# Sheet1.net
KiCad netlist of a schematic drawn in Altium Designer
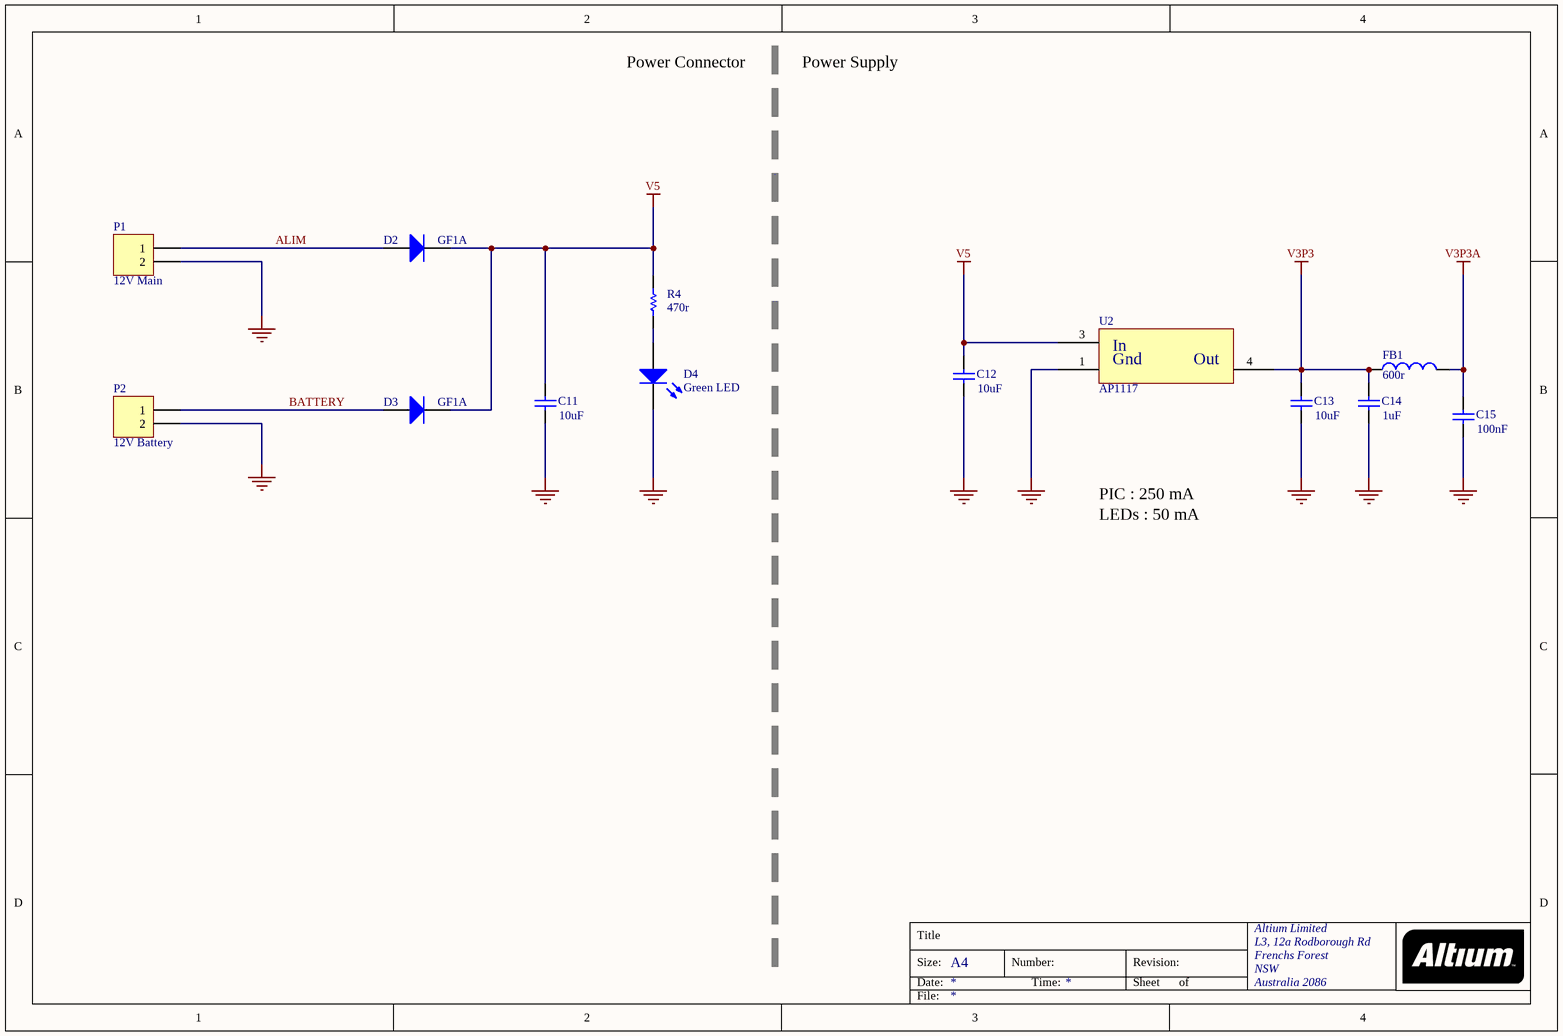
[diagram p0: Sheet1.SchDoc]

(export (version "E")
  (design (tool "Eeschema 10.0.6"))
  (components
    (comp (ref "C11")
      (value "10uF")
      (footprint "RAD-0.3")
      (description "Capacitor")
      (fields (field (name "PUBLISHER") "Altium Limited"))
      (libsource (lib "Miscellaneous Devices") (part "Cap"))
    )
    (comp (ref "C12")
      (value "10uF")
      (footprint "RAD-0.3")
      (description "Capacitor")
      (fields (field (name "Comment") "Cap") (field (name "PUBLISHER") "Altium Limited"))
      (libsource (lib "Miscellaneous Devices") (part "Cap"))
    )
    (comp (ref "C13")
      (value "10uF")
      (footprint "RAD-0.3")
      (description "Capacitor")
      (fields (field (name "Comment") "Cap") (field (name "PUBLISHER") "Altium Limited"))
      (libsource (lib "Miscellaneous Devices") (part "Cap"))
    )
    (comp (ref "C14")
      (value "1uF")
      (footprint "RAD-0.3")
      (description "Capacitor")
      (fields (field (name "Comment") "Cap") (field (name "PUBLISHER") "Altium Limited"))
      (libsource (lib "Miscellaneous Devices") (part "Cap"))
    )
    (comp (ref "C15")
      (value "100nF")
      (footprint "RAD-0.3")
      (description "Capacitor")
      (fields (field (name "Comment") "Cap") (field (name "PUBLISHER") "Altium Limited"))
      (libsource (lib "Miscellaneous Devices") (part "Cap"))
    )
    (comp (ref "D2")
      (value "GF1A")
      (footprint "SMC")
      (description "Default Diode")
      (fields (field (name "PUBLISHER") "Altium Limited"))
      (libsource (lib "Miscellaneous Devices") (part "Diode"))
    )
    (comp (ref "D3")
      (value "GF1A")
      (footprint "SMC")
      (description "Default Diode")
      (fields (field (name "PUBLISHER") "Altium Limited"))
      (libsource (lib "Miscellaneous Devices") (part "Diode"))
    )
    (comp (ref "D4")
      (value "Green LED")
      (footprint "LED-0")
      (description "Typical INFRARED GaAs LED")
      (fields (field (name "PUBLISHER") "Altium Limited"))
      (libsource (lib "Miscellaneous Devices") (part "LED0"))
    )
    (comp (ref "FB1")
      (value "600r")
      (footprint "0402-A")
      (description "Inductor")
      (fields (field (name "PUBLISHER") "Altium Limited"))
      (libsource (lib "Miscellaneous Devices") (part "Inductor"))
    )
    (comp (ref "P1")
      (value "12V Main")
      (footprint "HDR1X2H")
      (description "Header, 2-Pin, Right Angle")
      (fields (field (name "PUBLISHER") "Altium Limited"))
      (libsource (lib "Miscellaneous Connectors") (part "Header 2H"))
    )
    (comp (ref "P2")
      (value "12V Battery")
      (footprint "HDR1X2H")
      (description "Header, 2-Pin, Right Angle")
      (fields (field (name "PUBLISHER") "Altium Limited"))
      (libsource (lib "Miscellaneous Connectors") (part "Header 2H"))
    )
    (comp (ref "R4")
      (value "470r")
      (footprint "AXIAL-0.3")
      (description "Resistor")
      (fields (field (name "Comment") "Res1") (field (name "PUBLISHER") "Altium Limited"))
      (libsource (lib "Miscellaneous Devices") (part "Res1"))
    )
    (comp (ref "U2") (value "AP1117") (footprint "AP1117") (libsource (lib "SchlibNOUS") (part "AP1117")))
  )
  (nets
    (net (code "1") (name "/ALIM") (class "Default")
      (node (ref "D2") (pin "1") (pinfunction "A_1") (pintype "passive"))
      (node (ref "P1") (pin "1") (pinfunction "1_1") (pintype "passive"))
    )
    (net (code "2") (name "/BATTERY") (class "Default")
      (node (ref "D3") (pin "1") (pinfunction "A_1") (pintype "passive"))
      (node (ref "P2") (pin "1") (pinfunction "1_1") (pintype "passive"))
    )
    (net (code "3") (name "GND") (class "Default")
      (node (ref "C11") (pin "1") (pinfunction "1_1") (pintype "passive"))
      (node (ref "C12") (pin "1") (pinfunction "1_1") (pintype "passive"))
      (node (ref "C13") (pin "1") (pinfunction "1_1") (pintype "passive"))
      (node (ref "C14") (pin "1") (pinfunction "1_1") (pintype "passive"))
      (node (ref "C15") (pin "1") (pinfunction "1_1") (pintype "passive"))
      (node (ref "D4") (pin "2") (pinfunction "K_2") (pintype "passive"))
      (node (ref "P1") (pin "2") (pinfunction "2_2") (pintype "passive"))
      (node (ref "P2") (pin "2") (pinfunction "2_2") (pintype "passive"))
      (node (ref "U2") (pin "1") (pinfunction "1_1") (pintype "passive"))
    )
    (net (code "4") (name "Net-(D4-A)") (class "Default")
      (node (ref "D4") (pin "1") (pinfunction "A_1") (pintype "passive"))
      (node (ref "R4") (pin "1") (pinfunction "1_1") (pintype "passive"))
    )
    (net (code "5") (name "V3P3") (class "Default")
      (node (ref "C13") (pin "2") (pinfunction "2_2") (pintype "passive"))
      (node (ref "C14") (pin "2") (pinfunction "2_2") (pintype "passive"))
      (node (ref "FB1") (pin "1") (pinfunction "1_1") (pintype "passive"))
      (node (ref "U2") (pin "4") (pinfunction "4_4") (pintype "passive"))
    )
    (net (code "6") (name "V3P3A") (class "Default")
      (node (ref "C15") (pin "2") (pinfunction "2_2") (pintype "passive"))
      (node (ref "FB1") (pin "2") (pinfunction "2_2") (pintype "passive"))
    )
    (net (code "7") (name "V5") (class "Default")
      (node (ref "C11") (pin "2") (pinfunction "2_2") (pintype "passive"))
      (node (ref "C12") (pin "2") (pinfunction "2_2") (pintype "passive"))
      (node (ref "D2") (pin "2") (pinfunction "K_2") (pintype "passive"))
      (node (ref "D3") (pin "2") (pinfunction "K_2") (pintype "passive"))
      (node (ref "R4") (pin "2") (pinfunction "2_2") (pintype "passive"))
      (node (ref "U2") (pin "3") (pinfunction "3_3") (pintype "passive"))
    )
  )
)
